# 6DOF_CONTROLLER_Top.net
KiCad netlist of a schematic drawn in Altium Designer
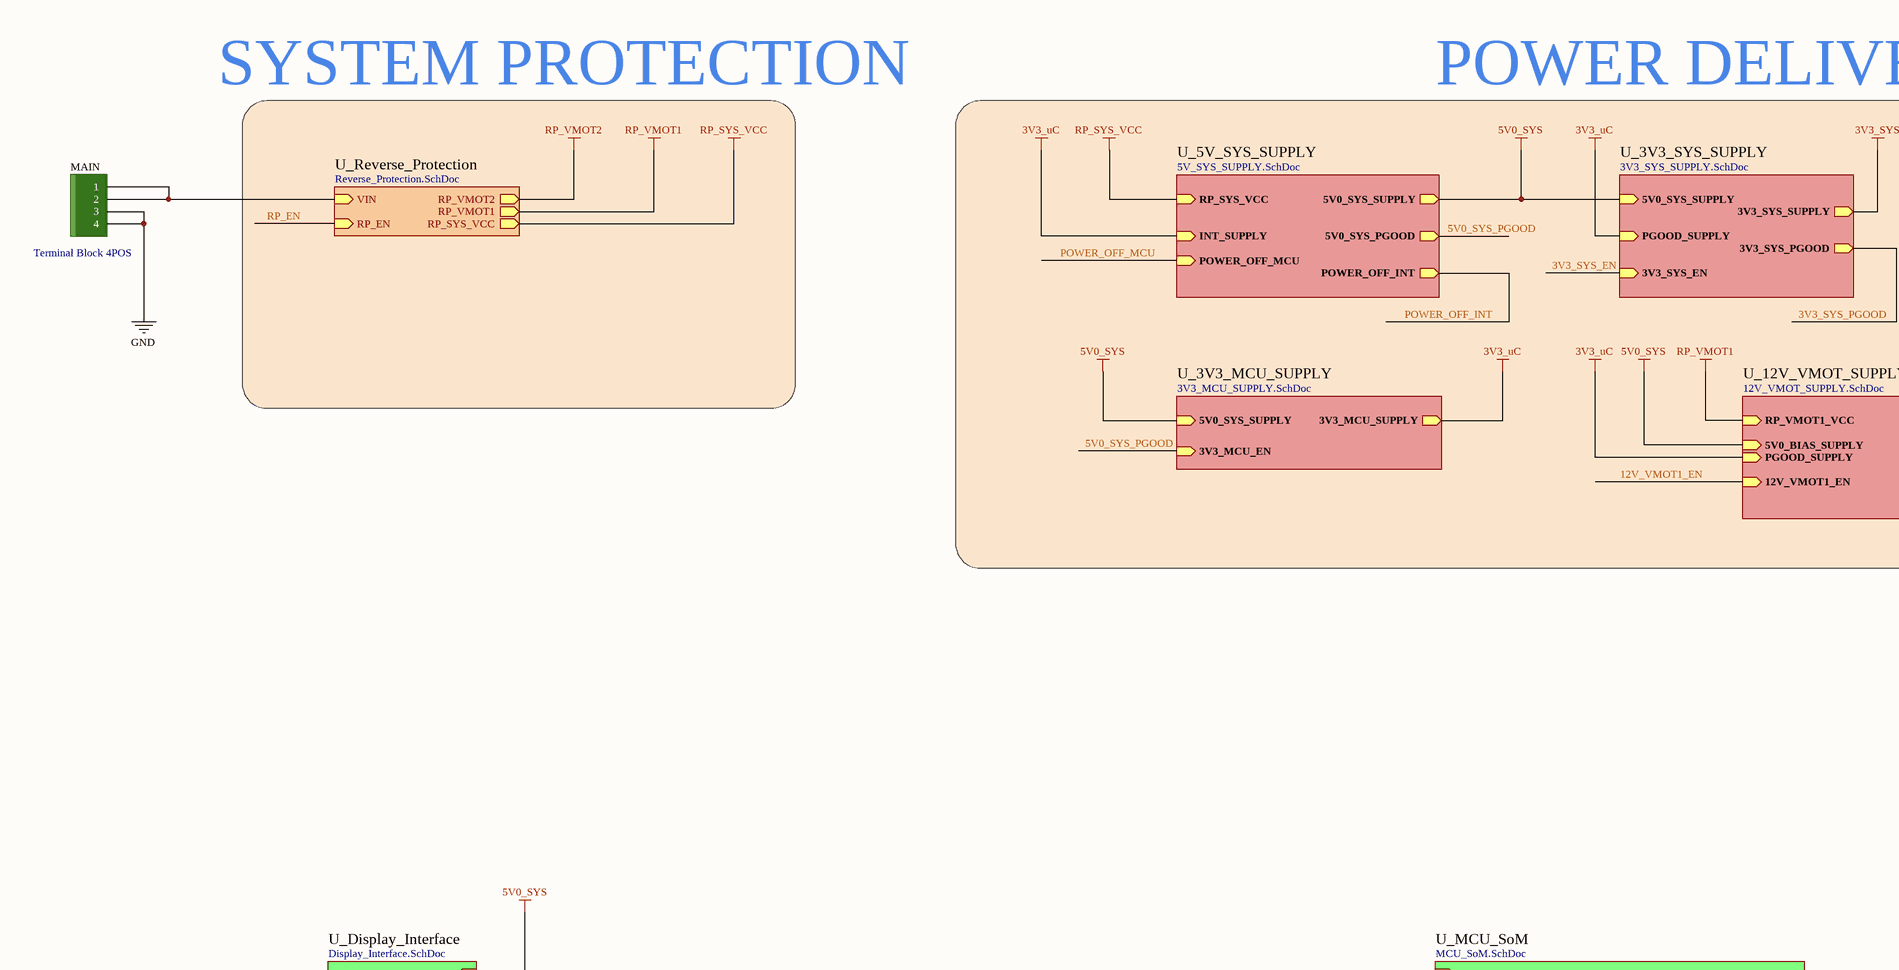
[diagram p0: 6DOF_CONTROLLER_Top.SchDoc, top left]
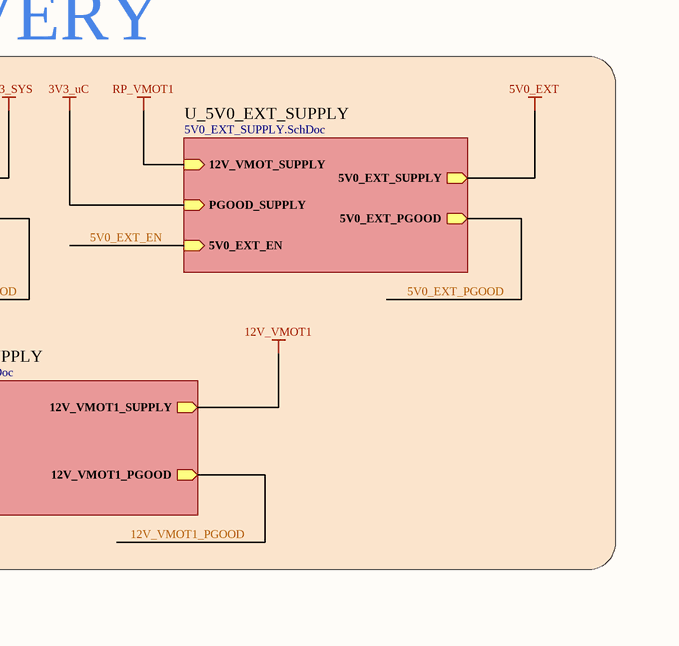
[diagram p1: 6DOF_CONTROLLER_Top.SchDoc, top right]
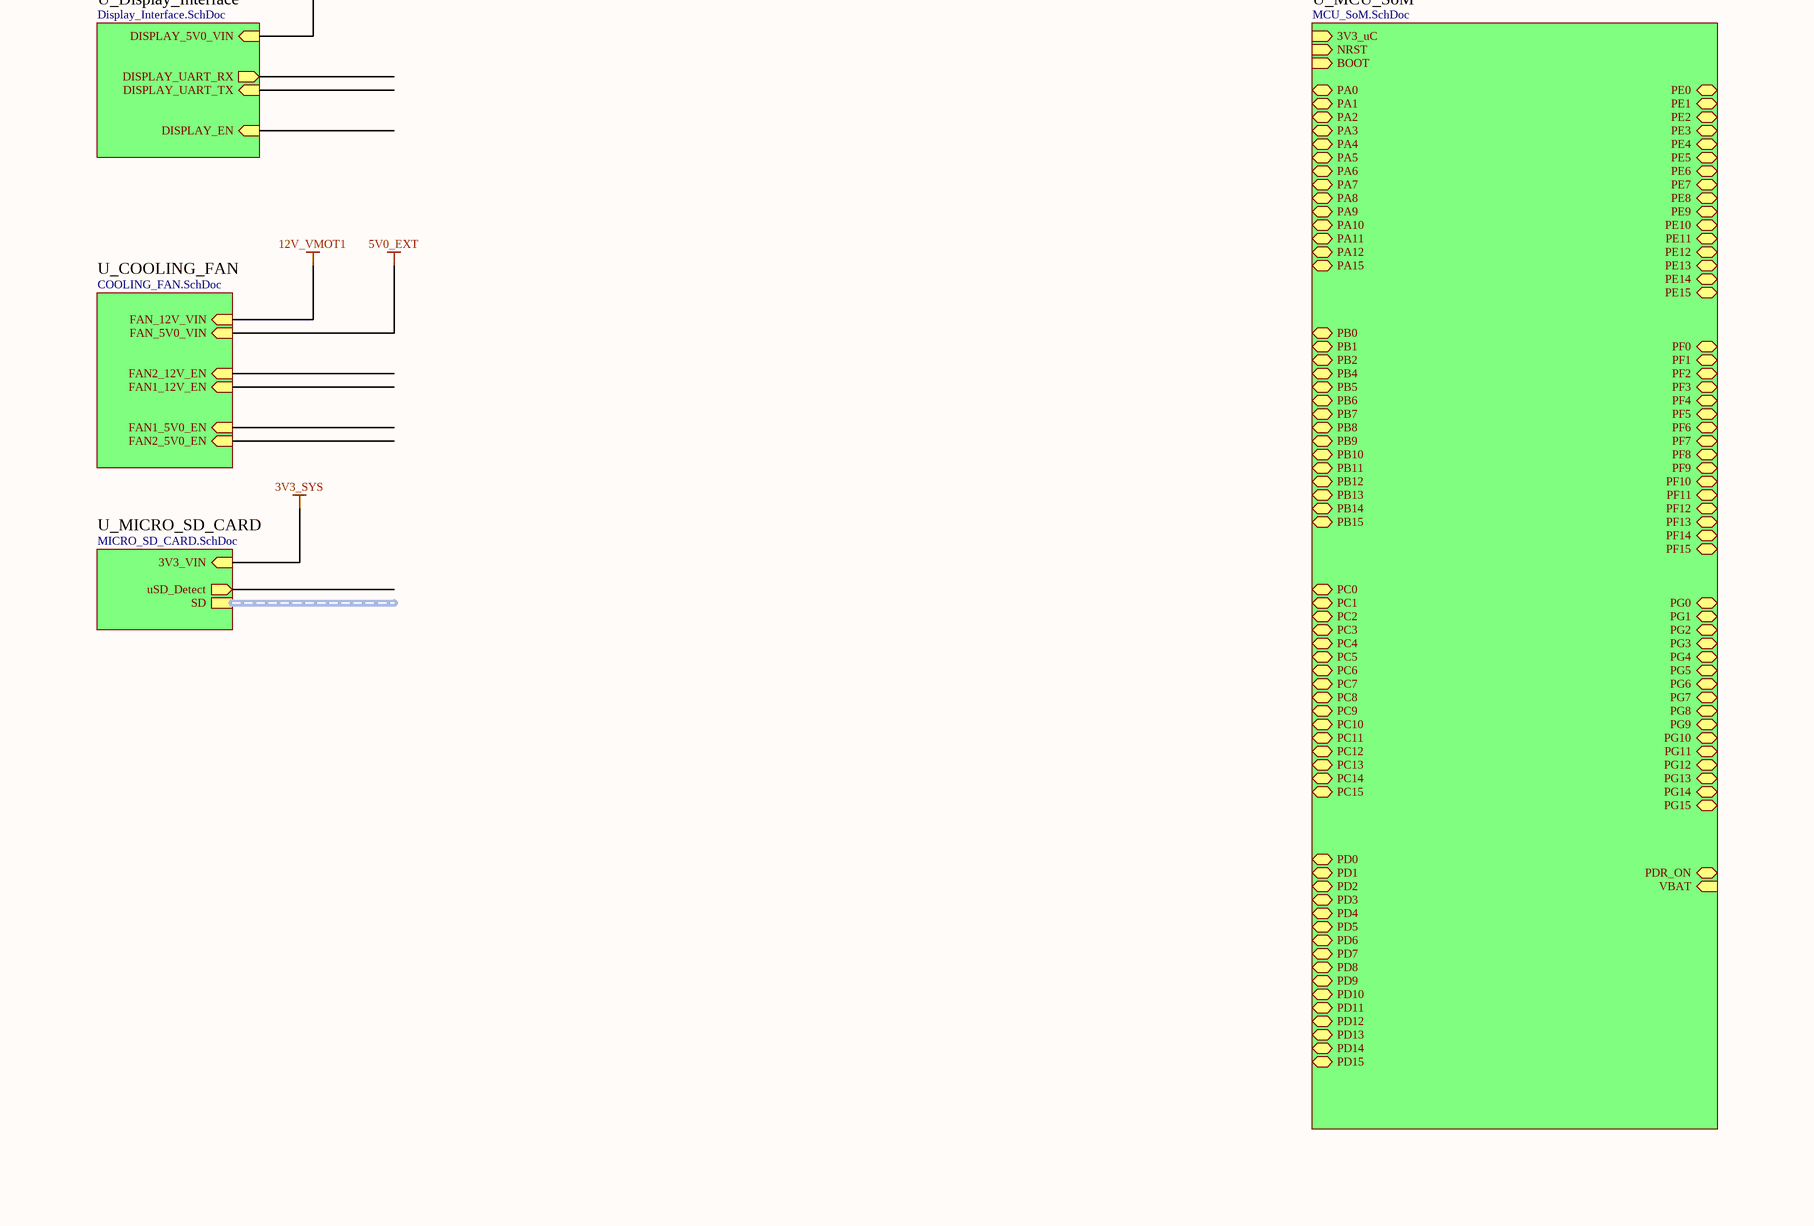
[diagram p2: 6DOF_CONTROLLER_Top.SchDoc, bottom left]
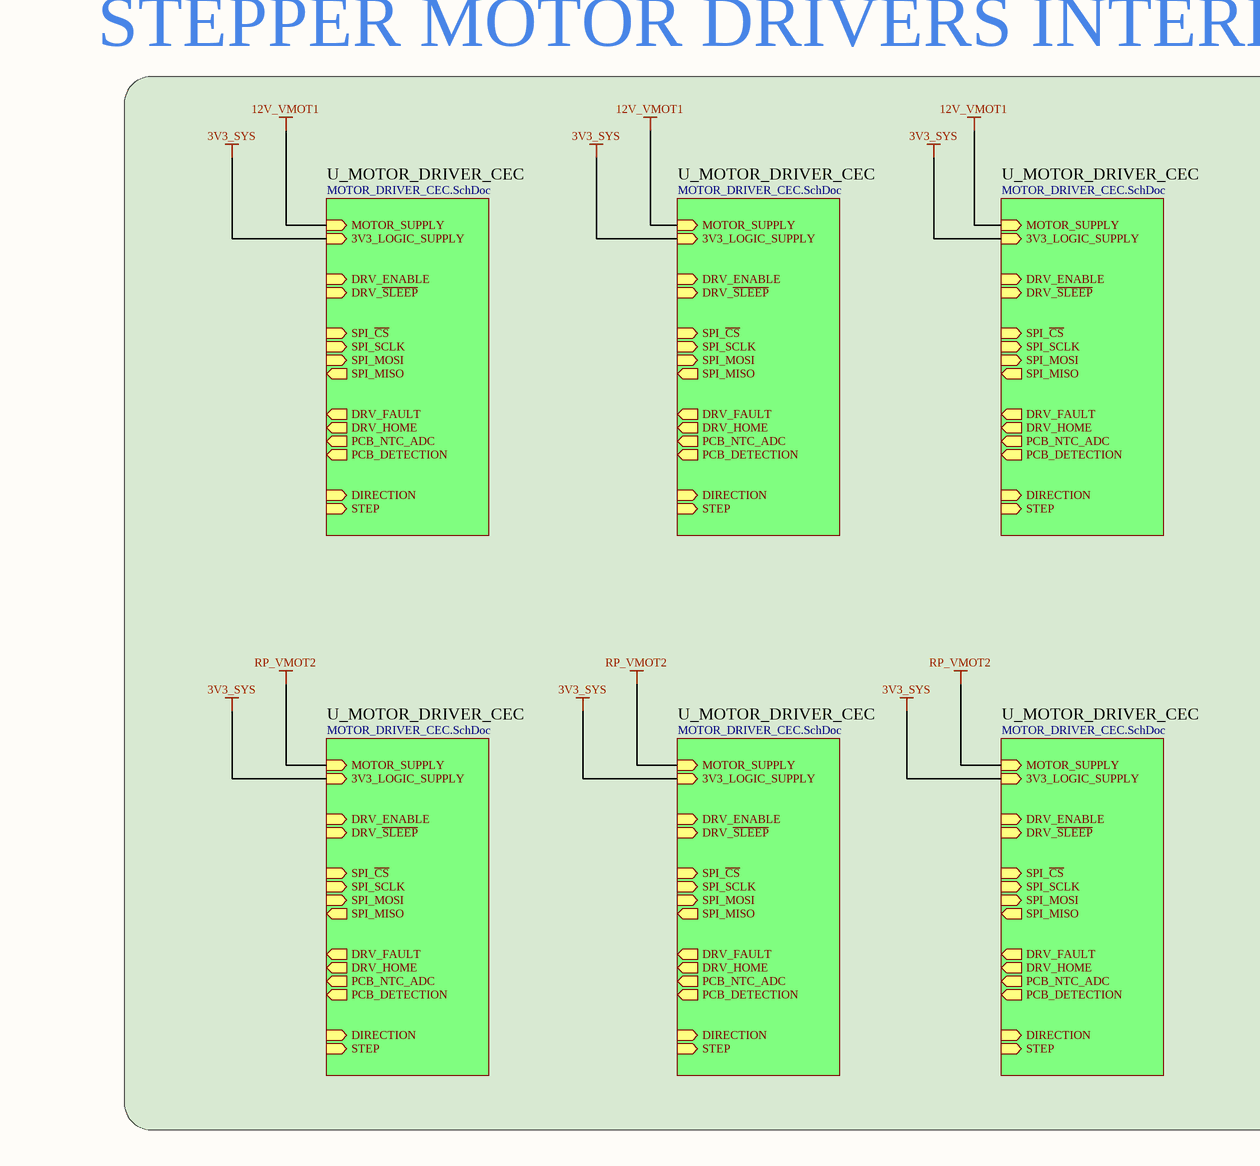
[diagram p3: 6DOF_CONTROLLER_Top.SchDoc, bottom right]

(export (version "E")
  (design (tool "Eeschema 10.0.6"))
  (components
    (comp (ref "MAIN")
      (value "Terminal Block 4POS")
      (footprint "TERM_BLOCK_5.08mm 4PIN")
      (description "XY2500R-D 250V 12A 5.08mm")
      (libsource (lib "ElectroMechanical") (part "00000011"))
    )
  )
  (nets
    (net (code "205") (name "/VIN") (class "Default")
      (node (ref "MAIN") (pin "1") (pinfunction "1_1") (pintype "passive"))
      (node (ref "MAIN") (pin "2") (pinfunction "2_2") (pintype "passive"))
    )
    (net (code "212") (name "GND") (class "Default")
      (node (ref "MAIN") (pin "3") (pinfunction "3_3") (pintype "passive"))
      (node (ref "MAIN") (pin "4") (pinfunction "4_4") (pintype "passive"))
    )
  )
)
